# ZED-F9P_NEO-D9S_Combo.net
KiCad netlist of a schematic drawn in EAGLE
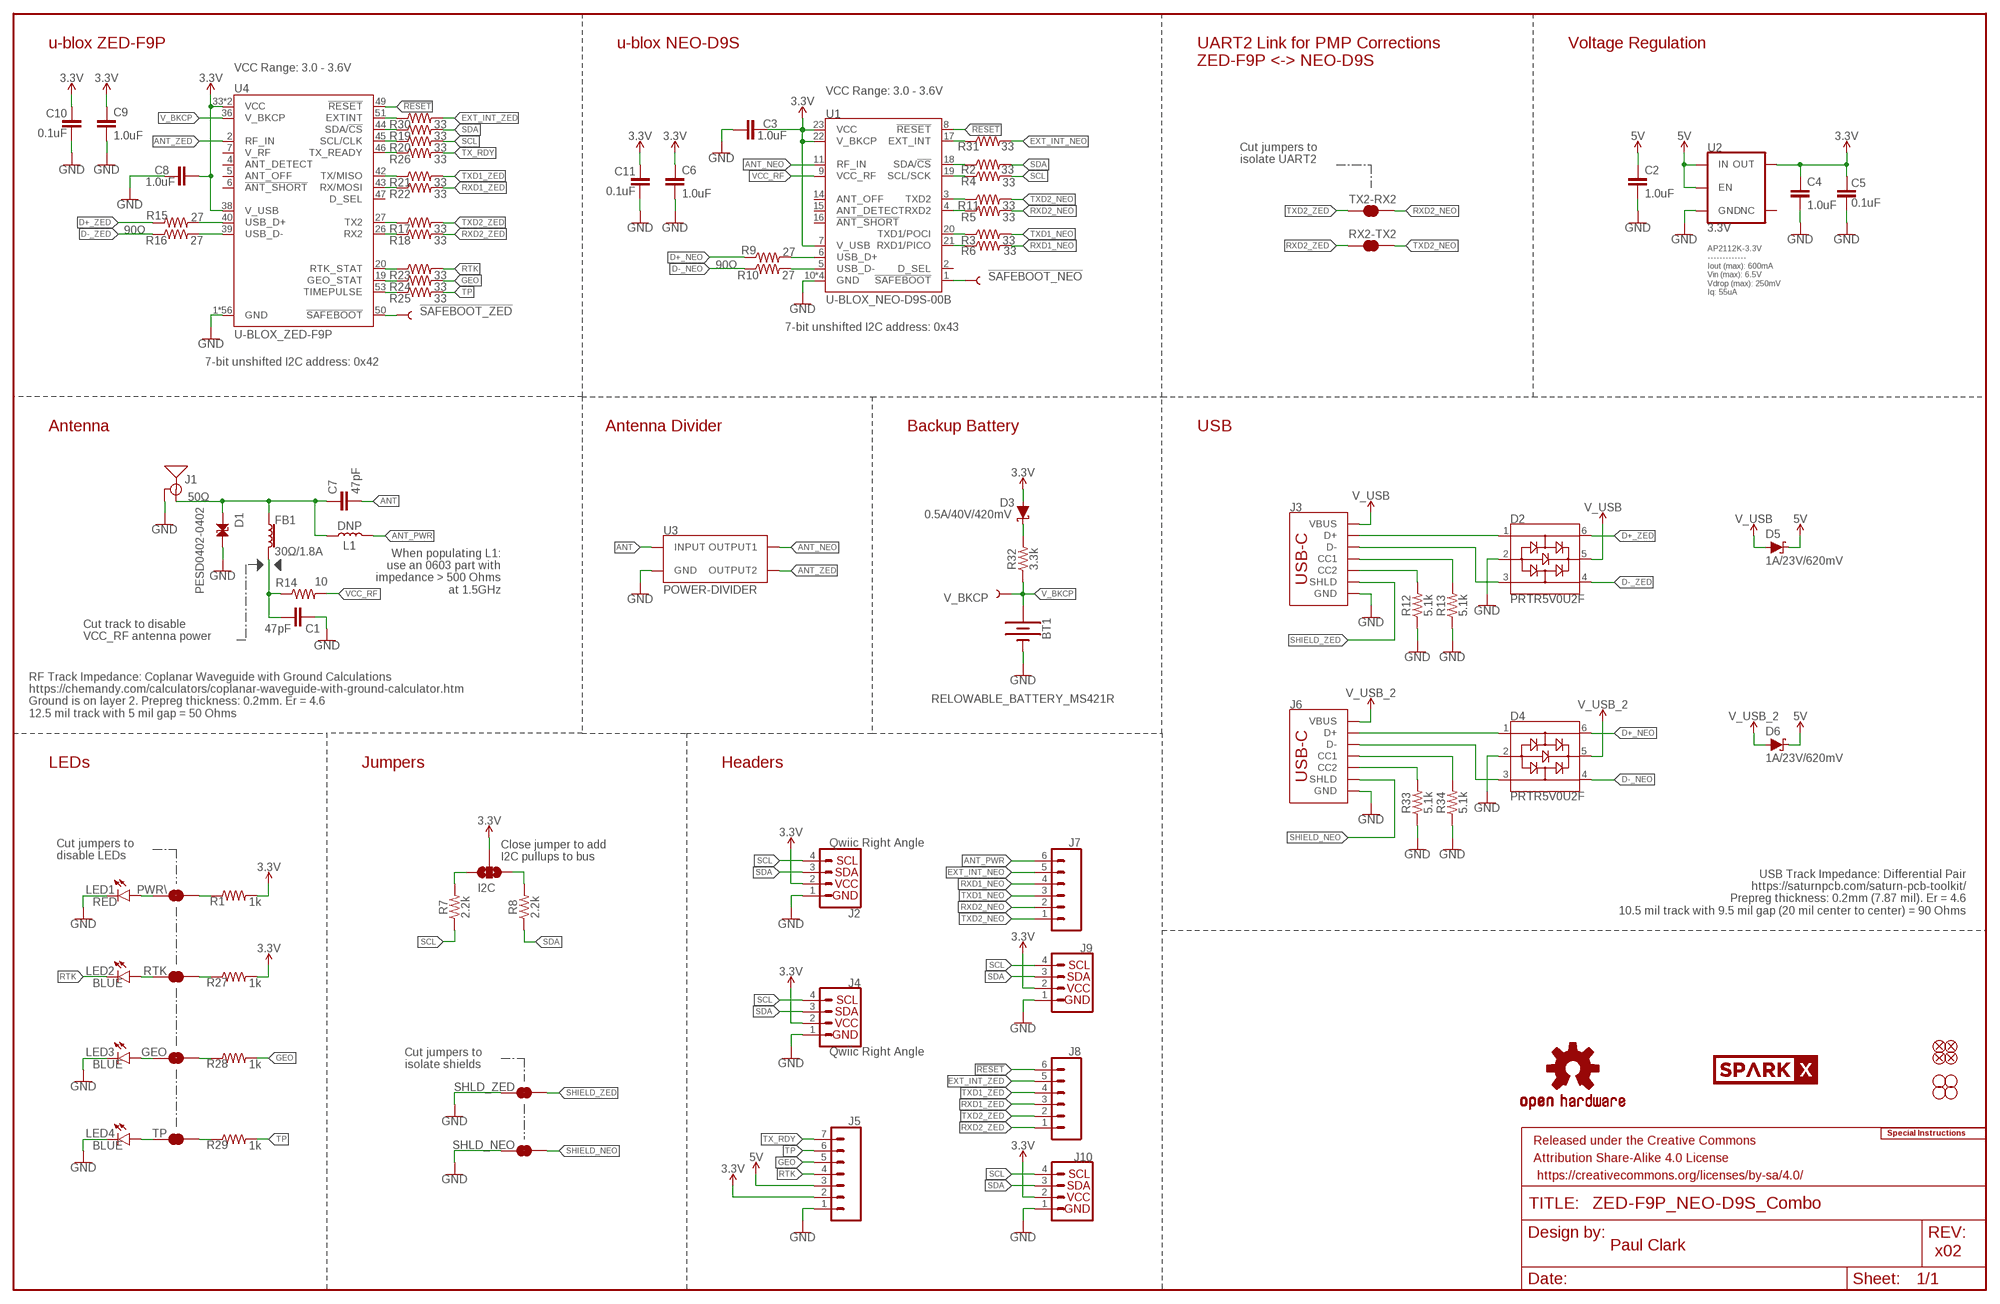
[diagram p0: schematic, sheet 1]

(export (version "E")
  (design (tool "Eeschema 10.0.6"))
  (components
    (comp (ref "!SAFEBOOT_NEO!")
      (value "TEST-POINTPOGO_PTH")
      (footprint "eagle-import:1X01_NO_SILK")
      (libsource (lib "eagle-import") (part "TEST-POINTPOGO_PTH"))
    )
    (comp (ref "!SAFEBOOT_ZED!")
      (value "TEST-POINTPOGO_PTH")
      (footprint "eagle-import:1X01_NO_SILK")
      (libsource (lib "eagle-import") (part "TEST-POINTPOGO_PTH"))
    )
    (comp (ref "BT1")
      (value "RELOWABLE_BATTERY_MS421R")
      (footprint "eagle-import:MS421R_IV03E")
      (libsource (lib "eagle-import") (part "RELOWABLE_BATTERY_MS421R"))
    )
    (comp (ref "C1")
      (value "47pF")
      (footprint "eagle-import:0603")
      (libsource (lib "eagle-import") (part "47PF-0603-50V-5%"))
    )
    (comp (ref "C2")
      (value "1.0uF")
      (footprint "eagle-import:0603")
      (libsource (lib "eagle-import") (part "1.0UF-0603-16V-10%"))
    )
    (comp (ref "C3")
      (value "1.0uF")
      (footprint "eagle-import:0603")
      (libsource (lib "eagle-import") (part "1.0UF-0603-16V-10%"))
    )
    (comp (ref "C4")
      (value "1.0uF")
      (footprint "eagle-import:0603")
      (libsource (lib "eagle-import") (part "1.0UF-0603-16V-10%"))
    )
    (comp (ref "C5")
      (value "0.1uF")
      (footprint "eagle-import:0603")
      (libsource (lib "eagle-import") (part "0.1UF-0603-25V-(+80/-20%)"))
    )
    (comp (ref "C6")
      (value "1.0uF")
      (footprint "eagle-import:0603")
      (libsource (lib "eagle-import") (part "1.0UF-0603-16V-10%"))
    )
    (comp (ref "C7")
      (value "47pF")
      (footprint "eagle-import:0603")
      (libsource (lib "eagle-import") (part "47PF-0603-50V-5%"))
    )
    (comp (ref "C8")
      (value "1.0uF")
      (footprint "eagle-import:0603")
      (libsource (lib "eagle-import") (part "1.0UF-0603-16V-10%"))
    )
    (comp (ref "C9")
      (value "1.0uF")
      (footprint "eagle-import:0603")
      (libsource (lib "eagle-import") (part "1.0UF-0603-16V-10%"))
    )
    (comp (ref "C10")
      (value "0.1uF")
      (footprint "eagle-import:0603")
      (libsource (lib "eagle-import") (part "0.1UF-0603-25V-(+80/-20%)"))
    )
    (comp (ref "C11")
      (value "0.1uF")
      (footprint "eagle-import:0603")
      (libsource (lib "eagle-import") (part "0.1UF-0603-25V-(+80/-20%)"))
    )
    (comp (ref "D1")
      (value "PESD0402-0402")
      (footprint "eagle-import:0402")
      (fields
        (field (name "DIGIKEY_PART") "PESD0402-140CT-ND")
        (field (name "MOUSE_PART") "650-PESD0402-140")
      )
      (libsource (lib "eagle-import") (part "PESD0402-0402"))
    )
    (comp (ref "D2")
      (value "PRTR5V0U2F")
      (footprint "eagle-import:SOT886")
      (libsource (lib "eagle-import") (part "PRTR5V0U2F"))
    )
    (comp (ref "D3")
      (value "0.5A/40V/420mV")
      (footprint "eagle-import:SOD-323")
      (libsource (lib "eagle-import") (part "DIODE-SCHOTTKY-PMEG4005EJ"))
    )
    (comp (ref "D4")
      (value "PRTR5V0U2F")
      (footprint "eagle-import:SOT886")
      (libsource (lib "eagle-import") (part "PRTR5V0U2F"))
    )
    (comp (ref "D5")
      (value "1A/23V/620mV")
      (footprint "eagle-import:SOD-323")
      (libsource (lib "eagle-import") (part "DIODE-SCHOTTKY-BAT20J"))
    )
    (comp (ref "D6")
      (value "1A/23V/620mV")
      (footprint "eagle-import:SOD-323")
      (libsource (lib "eagle-import") (part "DIODE-SCHOTTKY-BAT20J"))
    )
    (comp (ref "FB1")
      (value "30Ω/1.8A")
      (footprint "eagle-import:0603")
      (libsource (lib "eagle-import") (part "FERRITE_BEAD-0603"))
    )
    (comp (ref "FRAME2")
      (value "FRAME-LEDGER")
      (footprint "eagle-import:CREATIVE_COMMONS")
      (libsource (lib "eagle-import") (part "FRAME-LEDGER"))
    )
    (comp (ref "GEO")
      (value "JUMPER-SMT_2_NC_TRACE_SILK")
      (footprint "eagle-import:SMT-JUMPER_2_NC_TRACE_SILK")
      (libsource (lib "eagle-import") (part "JUMPER-SMT_2_NC_TRACE_SILK"))
    )
    (comp (ref "I2C")
      (value "JUMPER-SMT_3_NO_SILK")
      (footprint "eagle-import:SMT-JUMPER_3_NO_SILK")
      (libsource (lib "eagle-import") (part "JUMPER-SMT_3_NO_SILK"))
    )
    (comp (ref "J1")
      (value "ANTENNA-SMA-GROUNDEDEDGE_SMA")
      (footprint "eagle-import:SMA-EDGE")
      (libsource (lib "eagle-import") (part "ANTENNA-SMA-GROUNDEDEDGE_SMA"))
    )
    (comp (ref "J2")
      (value "Qwiic Right Angle")
      (footprint "eagle-import:JST04_1MM_RA")
      (libsource (lib "eagle-import") (part "I2C_STANDARDQWIIC"))
    )
    (comp (ref "J3")
      (value "USB Female Type C Connector")
      (footprint "eagle-import:USB-C-16P_4LAYER-PADS")
      (libsource (lib "eagle-import") (part "USB_C_4-LAYER_PADS"))
    )
    (comp (ref "J4")
      (value "Qwiic Right Angle")
      (footprint "eagle-import:JST04_1MM_RA")
      (libsource (lib "eagle-import") (part "I2C_STANDARDQWIIC"))
    )
    (comp (ref "J5")
      (value "CONN_07NO_SILK")
      (footprint "eagle-import:1X07_NO_SILK")
      (libsource (lib "eagle-import") (part "CONN_07NO_SILK"))
    )
    (comp (ref "J6")
      (value "USB Female Type C Connector")
      (footprint "eagle-import:USB-C-16P_4LAYER-PADS")
      (libsource (lib "eagle-import") (part "USB_C_4-LAYER_PADS"))
    )
    (comp (ref "J7")
      (value "CONN_06NO_SILK_FEMALE_PTH")
      (footprint "eagle-import:1X06_NO_SILK")
      (libsource (lib "eagle-import") (part "CONN_06NO_SILK_FEMALE_PTH"))
    )
    (comp (ref "J8")
      (value "CONN_06NO_SILK_FEMALE_PTH")
      (footprint "eagle-import:1X06_NO_SILK")
      (libsource (lib "eagle-import") (part "CONN_06NO_SILK_FEMALE_PTH"))
    )
    (comp (ref "J9")
      (value "I2C_STANDARD_NO_SILK")
      (footprint "eagle-import:1X04_NO_SILK")
      (libsource (lib "eagle-import") (part "I2C_STANDARD_NO_SILK"))
    )
    (comp (ref "J10")
      (value "I2C_STANDARD_NO_SILK")
      (footprint "eagle-import:1X04_NO_SILK")
      (libsource (lib "eagle-import") (part "I2C_STANDARD_NO_SILK"))
    )
    (comp (ref "JP21")
      (value "FIDUCIALUFIDUCIAL")
      (footprint "eagle-import:MICRO-FIDUCIAL")
      (libsource (lib "eagle-import") (part "FIDUCIALUFIDUCIAL"))
    )
    (comp (ref "JP31")
      (value "STAND-OFF")
      (footprint "eagle-import:STAND-OFF")
      (libsource (lib "eagle-import") (part "STAND-OFF"))
    )
    (comp (ref "JP41")
      (value "STAND-OFF")
      (footprint "eagle-import:STAND-OFF")
      (libsource (lib "eagle-import") (part "STAND-OFF"))
    )
    (comp (ref "JP61")
      (value "FIDUCIALUFIDUCIAL")
      (footprint "eagle-import:MICRO-FIDUCIAL")
      (libsource (lib "eagle-import") (part "FIDUCIALUFIDUCIAL"))
    )
    (comp (ref "JP71")
      (value "FIDUCIALUFIDUCIAL")
      (footprint "eagle-import:MICRO-FIDUCIAL")
      (libsource (lib "eagle-import") (part "FIDUCIALUFIDUCIAL"))
    )
    (comp (ref "JP81")
      (value "FIDUCIALUFIDUCIAL")
      (footprint "eagle-import:MICRO-FIDUCIAL")
      (libsource (lib "eagle-import") (part "FIDUCIALUFIDUCIAL"))
    )
    (comp (ref "JP91")
      (value "STAND-OFF")
      (footprint "eagle-import:STAND-OFF")
      (libsource (lib "eagle-import") (part "STAND-OFF"))
    )
    (comp (ref "JP101")
      (value "STAND-OFF")
      (footprint "eagle-import:STAND-OFF")
      (libsource (lib "eagle-import") (part "STAND-OFF"))
    )
    (comp (ref "L1")
      (value "DNP")
      (footprint "eagle-import:0603_NO-CREAM")
      (libsource (lib "eagle-import") (part "DNP-0603_NO-CREAM"))
    )
    (comp (ref "LED1")
      (value "RED")
      (footprint "eagle-import:LED-0603")
      (libsource (lib "eagle-import") (part "LED-RED0603"))
    )
    (comp (ref "LED2")
      (value "BLUE")
      (footprint "eagle-import:LED-0603")
      (libsource (lib "eagle-import") (part "LED-BLUE0603"))
    )
    (comp (ref "LED3")
      (value "BLUE")
      (footprint "eagle-import:LED-0603")
      (libsource (lib "eagle-import") (part "LED-BLUE0603"))
    )
    (comp (ref "LED4")
      (value "BLUE")
      (footprint "eagle-import:LED-0603")
      (libsource (lib "eagle-import") (part "LED-BLUE0603"))
    )
    (comp (ref "LOGO4")
      (value "OSHW-LOGOS")
      (footprint "eagle-import:OSHW-LOGO-S")
      (libsource (lib "eagle-import") (part "OSHW-LOGOS"))
    )
    (comp (ref "LOGO5")
      (value "SPECIAL_INSTRUCTIONS-ORDERING")
      (footprint "eagle-import:ORDERING_INSTRUCTIONS")
      (libsource (lib "eagle-import") (part "SPECIAL_INSTRUCTIONS-ORDERING"))
    )
    (comp (ref "PWR\\")
      (value "JUMPER-SMT_2_NC_TRACE_SILK")
      (footprint "eagle-import:SMT-JUMPER_2_NC_TRACE_SILK")
      (libsource (lib "eagle-import") (part "JUMPER-SMT_2_NC_TRACE_SILK"))
    )
    (comp (ref "R1")
      (value "1k")
      (footprint "eagle-import:0603")
      (libsource (lib "eagle-import") (part "1KOHM-0603-1/10W-1%"))
    )
    (comp (ref "R2")
      (value "33")
      (footprint "eagle-import:0603")
      (libsource (lib "eagle-import") (part "33OHM-0603-1/10W-1%"))
    )
    (comp (ref "R3")
      (value "33")
      (footprint "eagle-import:0603")
      (libsource (lib "eagle-import") (part "33OHM-0603-1/10W-1%"))
    )
    (comp (ref "R4")
      (value "33")
      (footprint "eagle-import:0603")
      (libsource (lib "eagle-import") (part "33OHM-0603-1/10W-1%"))
    )
    (comp (ref "R5")
      (value "33")
      (footprint "eagle-import:0603")
      (libsource (lib "eagle-import") (part "33OHM-0603-1/10W-1%"))
    )
    (comp (ref "R6")
      (value "33")
      (footprint "eagle-import:0603")
      (libsource (lib "eagle-import") (part "33OHM-0603-1/10W-1%"))
    )
    (comp (ref "R7")
      (value "2.2k")
      (footprint "eagle-import:0603")
      (libsource (lib "eagle-import") (part "2.2KOHM-0603-1/10W-1%"))
    )
    (comp (ref "R8")
      (value "2.2k")
      (footprint "eagle-import:0603")
      (libsource (lib "eagle-import") (part "2.2KOHM-0603-1/10W-1%"))
    )
    (comp (ref "R9")
      (value "27")
      (footprint "eagle-import:0603")
      (libsource (lib "eagle-import") (part "27OHM-0603-1/10W-1%"))
    )
    (comp (ref "R10")
      (value "27")
      (footprint "eagle-import:0603")
      (libsource (lib "eagle-import") (part "27OHM-0603-1/10W-1%"))
    )
    (comp (ref "R11")
      (value "33")
      (footprint "eagle-import:0603")
      (libsource (lib "eagle-import") (part "33OHM-0603-1/10W-1%"))
    )
    (comp (ref "R12")
      (value "5.1k")
      (footprint "eagle-import:0603")
      (libsource (lib "eagle-import") (part "5.1KOHM5.1KOHM-0603-1/10W-1%"))
    )
    (comp (ref "R13")
      (value "5.1k")
      (footprint "eagle-import:0603")
      (libsource (lib "eagle-import") (part "5.1KOHM5.1KOHM-0603-1/10W-1%"))
    )
    (comp (ref "R14")
      (value "10")
      (footprint "eagle-import:0603")
      (libsource (lib "eagle-import") (part "10OHM-0603-1/10W-1%"))
    )
    (comp (ref "R15")
      (value "27")
      (footprint "eagle-import:0603")
      (libsource (lib "eagle-import") (part "27OHM-0603-1/10W-1%"))
    )
    (comp (ref "R16")
      (value "27")
      (footprint "eagle-import:0603")
      (libsource (lib "eagle-import") (part "27OHM-0603-1/10W-1%"))
    )
    (comp (ref "R17")
      (value "33")
      (footprint "eagle-import:0603")
      (libsource (lib "eagle-import") (part "33OHM-0603-1/10W-1%"))
    )
    (comp (ref "R18")
      (value "33")
      (footprint "eagle-import:0603")
      (libsource (lib "eagle-import") (part "33OHM-0603-1/10W-1%"))
    )
    (comp (ref "R19")
      (value "33")
      (footprint "eagle-import:0603")
      (libsource (lib "eagle-import") (part "33OHM-0603-1/10W-1%"))
    )
    (comp (ref "R20")
      (value "33")
      (footprint "eagle-import:0603")
      (libsource (lib "eagle-import") (part "33OHM-0603-1/10W-1%"))
    )
    (comp (ref "R21")
      (value "33")
      (footprint "eagle-import:0603")
      (libsource (lib "eagle-import") (part "33OHM-0603-1/10W-1%"))
    )
    (comp (ref "R22")
      (value "33")
      (footprint "eagle-import:0603")
      (libsource (lib "eagle-import") (part "33OHM-0603-1/10W-1%"))
    )
    (comp (ref "R23")
      (value "33")
      (footprint "eagle-import:0603")
      (libsource (lib "eagle-import") (part "33OHM-0603-1/10W-1%"))
    )
    (comp (ref "R24")
      (value "33")
      (footprint "eagle-import:0603")
      (libsource (lib "eagle-import") (part "33OHM-0603-1/10W-1%"))
    )
    (comp (ref "R25")
      (value "33")
      (footprint "eagle-import:0603")
      (libsource (lib "eagle-import") (part "33OHM-0603-1/10W-1%"))
    )
    (comp (ref "R26")
      (value "33")
      (footprint "eagle-import:0603")
      (libsource (lib "eagle-import") (part "33OHM-0603-1/10W-1%"))
    )
    (comp (ref "R27")
      (value "1k")
      (footprint "eagle-import:0603")
      (libsource (lib "eagle-import") (part "1KOHM-0603-1/10W-1%"))
    )
    (comp (ref "R28")
      (value "1k")
      (footprint "eagle-import:0603")
      (libsource (lib "eagle-import") (part "1KOHM-0603-1/10W-1%"))
    )
    (comp (ref "R29")
      (value "1k")
      (footprint "eagle-import:0603")
      (libsource (lib "eagle-import") (part "1KOHM-0603-1/10W-1%"))
    )
    (comp (ref "R30")
      (value "33")
      (footprint "eagle-import:0603")
      (libsource (lib "eagle-import") (part "33OHM-0603-1/10W-1%"))
    )
    (comp (ref "R31")
      (value "33")
      (footprint "eagle-import:0603")
      (libsource (lib "eagle-import") (part "33OHM-0603-1/10W-1%"))
    )
    (comp (ref "R32")
      (value "3.3k")
      (footprint "eagle-import:0603")
      (libsource (lib "eagle-import") (part "3.3KOHM-0603-1/10W-1%"))
    )
    (comp (ref "R33")
      (value "5.1k")
      (footprint "eagle-import:0603")
      (libsource (lib "eagle-import") (part "5.1KOHM5.1KOHM-0603-1/10W-1%"))
    )
    (comp (ref "R34")
      (value "5.1k")
      (footprint "eagle-import:0603")
      (libsource (lib "eagle-import") (part "5.1KOHM5.1KOHM-0603-1/10W-1%"))
    )
    (comp (ref "RTK")
      (value "JUMPER-SMT_2_NC_TRACE_SILK")
      (footprint "eagle-import:SMT-JUMPER_2_NC_TRACE_SILK")
      (libsource (lib "eagle-import") (part "JUMPER-SMT_2_NC_TRACE_SILK"))
    )
    (comp (ref "RX2-TX2")
      (value "JUMPER-SMT_2_NC_TRACE_SILK")
      (footprint "eagle-import:SMT-JUMPER_2_NC_TRACE_SILK")
      (libsource (lib "eagle-import") (part "JUMPER-SMT_2_NC_TRACE_SILK"))
    )
    (comp (ref "SHLD_NEO")
      (value "JUMPER-SMT_2_NC_TRACE_SILK")
      (footprint "eagle-import:SMT-JUMPER_2_NC_TRACE_SILK")
      (libsource (lib "eagle-import") (part "JUMPER-SMT_2_NC_TRACE_SILK"))
    )
    (comp (ref "SHLD_ZED")
      (value "JUMPER-SMT_2_NC_TRACE_SILK")
      (footprint "eagle-import:SMT-JUMPER_2_NC_TRACE_SILK")
      (libsource (lib "eagle-import") (part "JUMPER-SMT_2_NC_TRACE_SILK"))
    )
    (comp (ref "TP")
      (value "JUMPER-SMT_2_NC_TRACE_SILK")
      (footprint "eagle-import:SMT-JUMPER_2_NC_TRACE_SILK")
      (libsource (lib "eagle-import") (part "JUMPER-SMT_2_NC_TRACE_SILK"))
    )
    (comp (ref "TX2-RX2")
      (value "JUMPER-SMT_2_NC_TRACE_SILK")
      (footprint "eagle-import:SMT-JUMPER_2_NC_TRACE_SILK")
      (libsource (lib "eagle-import") (part "JUMPER-SMT_2_NC_TRACE_SILK"))
    )
    (comp (ref "U$77")
      (value "SPARKX-LOGO4")
      (footprint "eagle-import:SPARKX-MEDIUM")
      (libsource (lib "eagle-import") (part "SPARKX-LOGO4"))
    )
    (comp (ref "U$78")
      (value "SPARKX-LOGO4")
      (footprint "eagle-import:SPARKX-MEDIUM")
      (libsource (lib "eagle-import") (part "SPARKX-LOGO4"))
    )
    (comp (ref "U1")
      (value "U-BLOX_NEO-D9S-00B")
      (footprint "eagle-import:NEO-M9N_M8T_M8U_D9S")
      (libsource (lib "eagle-import") (part "U-BLOX_NEO-D9S-00B"))
    )
    (comp (ref "U2")
      (value "3.3V")
      (footprint "eagle-import:SOT23-5")
      (libsource (lib "eagle-import") (part "V_REG_AP2112K-3.3V"))
    )
    (comp (ref "U3")
      (value "POWER-DIVIDER")
      (footprint "eagle-import:PD0922J5050S2HF_ANA")
      (fields (field (name "MANUFACTURER_PART_NUMBER") "PD0922J5050S2HF"))
      (libsource (lib "eagle-import") (part "POWER-DIVIDER"))
    )
    (comp (ref "U4")
      (value "U-BLOX_ZED-F9P")
      (footprint "eagle-import:ZED-F9P")
      (libsource (lib "eagle-import") (part "U-BLOX_ZED-F9P"))
    )
    (comp (ref "V_BKCP")
      (value "TEST-POINT3X5")
      (footprint "eagle-import:PAD.03X.05")
      (libsource (lib "eagle-import") (part "TEST-POINT3X5"))
    )
  )
  (nets
    (net (code "1") (name "/~{RESET}") (class "Default")
      (node (ref "J8") (pin "6") (pinfunction "6_6") (pintype "passive"))
      (node (ref "U1") (pin "8") (pinfunction "~{RESET}_8") (pintype "input"))
      (node (ref "U4") (pin "49") (pinfunction "~{RESET}_49") (pintype "bidirectional"))
    )
    (net (code "2") (name "3.3V") (class "Default")
      (node (ref "C10") (pin "2") (pinfunction "2_2") (pintype "passive"))
      (node (ref "C11") (pin "2") (pinfunction "2_2") (pintype "passive"))
      (node (ref "C3") (pin "1") (pinfunction "1_1") (pintype "passive"))
      (node (ref "C4") (pin "1") (pinfunction "1_1") (pintype "passive"))
      (node (ref "C5") (pin "2") (pinfunction "2_2") (pintype "passive"))
      (node (ref "C6") (pin "1") (pinfunction "1_1") (pintype "passive"))
      (node (ref "C8") (pin "2") (pinfunction "2_2") (pintype "passive"))
      (node (ref "C9") (pin "1") (pinfunction "1_1") (pintype "passive"))
      (node (ref "D3") (pin "A") (pinfunction "A_A") (pintype "passive"))
      (node (ref "I2C") (pin "2") (pinfunction "2_2") (pintype "passive"))
      (node (ref "J10") (pin "2") (pinfunction "2_2") (pintype "power_in"))
      (node (ref "J2") (pin "2") (pinfunction "2_2") (pintype "power_in"))
      (node (ref "J4") (pin "2") (pinfunction "2_2") (pintype "power_in"))
      (node (ref "J5") (pin "2") (pinfunction "2_2") (pintype "passive"))
      (node (ref "J9") (pin "2") (pinfunction "2_2") (pintype "power_in"))
      (node (ref "R1") (pin "2") (pinfunction "2_2") (pintype "passive"))
      (node (ref "R27") (pin "2") (pinfunction "2_2") (pintype "passive"))
      (node (ref "U1") (pin "22") (pinfunction "V_BKCP_22") (pintype "power_in"))
      (node (ref "U1") (pin "23") (pinfunction "VCC_23") (pintype "power_in"))
      (node (ref "U1") (pin "7") (pinfunction "V_USB_7") (pintype "power_in"))
      (node (ref "U2") (pin "5") (pinfunction "OUT_5") (pintype "passive"))
      (node (ref "U4") (pin "33") (pinfunction "VCC_33") (pintype "bidirectional"))
      (node (ref "U4") (pin "34") (pinfunction "VCC_34") (pintype "bidirectional"))
      (node (ref "U4") (pin "38") (pinfunction "V_USB_38") (pintype "bidirectional"))
    )
    (net (code "3") (name "5V") (class "Default")
      (node (ref "C2") (pin "1") (pinfunction "1_1") (pintype "passive"))
      (node (ref "D5") (pin "C") (pinfunction "C_C") (pintype "passive"))
      (node (ref "D6") (pin "C") (pinfunction "C_C") (pintype "passive"))
      (node (ref "J5") (pin "3") (pinfunction "3_3") (pintype "passive"))
      (node (ref "U2") (pin "1") (pinfunction "IN_1") (pintype "input"))
      (node (ref "U2") (pin "3") (pinfunction "EN_3") (pintype "input"))
    )
    (net (code "4") (name "ANT") (class "Default")
      (node (ref "C7") (pin "2") (pinfunction "2_2") (pintype "passive"))
      (node (ref "U3") (pin "2") (pinfunction "INPUT_2") (pintype "input"))
    )
    (net (code "5") (name "ANT_NEO") (class "Default")
      (node (ref "U1") (pin "11") (pinfunction "RF_IN_11") (pintype "input"))
      (node (ref "U3") (pin "4") (pinfunction "OUTPUT1_4") (pintype "output"))
    )
    (net (code "6") (name "ANT_PWR") (class "Default")
      (node (ref "J7") (pin "6") (pinfunction "6_6") (pintype "passive"))
      (node (ref "L1") (pin "2") (pinfunction "2_2") (pintype "passive"))
    )
    (net (code "7") (name "ANT_ZED") (class "Default")
      (node (ref "U3") (pin "6") (pinfunction "OUTPUT2_6") (pintype "output"))
      (node (ref "U4") (pin "2") (pinfunction "RF_IN_2") (pintype "bidirectional"))
    )
    (net (code "8") (name "D+_NEO") (class "Default")
      (node (ref "D4") (pin "6") (pinfunction "6_6") (pintype "bidirectional"))
      (node (ref "R9") (pin "1") (pinfunction "1_1") (pintype "passive"))
    )
    (net (code "9") (name "D+_ZED") (class "Default")
      (node (ref "D2") (pin "6") (pinfunction "6_6") (pintype "bidirectional"))
      (node (ref "R15") (pin "1") (pinfunction "1_1") (pintype "passive"))
    )
    (net (code "10") (name "D-_NEO") (class "Default")
      (node (ref "D4") (pin "4") (pinfunction "4_4") (pintype "bidirectional"))
      (node (ref "R10") (pin "1") (pinfunction "1_1") (pintype "passive"))
    )
    (net (code "11") (name "D-_ZED") (class "Default")
      (node (ref "D2") (pin "4") (pinfunction "4_4") (pintype "bidirectional"))
      (node (ref "R16") (pin "1") (pinfunction "1_1") (pintype "passive"))
    )
    (net (code "12") (name "EXT_INT_NEO") (class "Default")
      (node (ref "J7") (pin "5") (pinfunction "5_5") (pintype "passive"))
      (node (ref "R31") (pin "2") (pinfunction "2_2") (pintype "passive"))
    )
    (net (code "13") (name "EXT_INT_ZED") (class "Default")
      (node (ref "J8") (pin "5") (pinfunction "5_5") (pintype "passive"))
      (node (ref "R30") (pin "2") (pinfunction "2_2") (pintype "passive"))
    )
    (net (code "14") (name "GEO") (class "Default")
      (node (ref "J5") (pin "5") (pinfunction "5_5") (pintype "passive"))
      (node (ref "R24") (pin "2") (pinfunction "2_2") (pintype "passive"))
      (node (ref "R28") (pin "2") (pinfunction "2_2") (pintype "passive"))
    )
    (net (code "15") (name "GND") (class "Default")
      (node (ref "BT1") (pin "-") (pinfunction "-_-") (pintype "power_in"))
      (node (ref "C1") (pin "2") (pinfunction "2_2") (pintype "passive"))
      (node (ref "C10") (pin "1") (pinfunction "1_1") (pintype "passive"))
      (node (ref "C11") (pin "1") (pinfunction "1_1") (pintype "passive"))
      (node (ref "C2") (pin "2") (pinfunction "2_2") (pintype "passive"))
      (node (ref "C3") (pin "2") (pinfunction "2_2") (pintype "passive"))
      (node (ref "C4") (pin "2") (pinfunction "2_2") (pintype "passive"))
      (node (ref "C5") (pin "1") (pinfunction "1_1") (pintype "passive"))
      (node (ref "C6") (pin "2") (pinfunction "2_2") (pintype "passive"))
      (node (ref "C8") (pin "1") (pinfunction "1_1") (pintype "passive"))
      (node (ref "C9") (pin "2") (pinfunction "2_2") (pintype "passive"))
      (node (ref "D1") (pin "2") (pinfunction "2_2") (pintype "bidirectional"))
      (node (ref "D2") (pin "2") (pinfunction "2_2") (pintype "power_in"))
      (node (ref "D4") (pin "2") (pinfunction "2_2") (pintype "power_in"))
      (node (ref "J1") (pin "GND@0") (pinfunction "GND_GND@0") (pintype "bidirectional"))
      (node (ref "J1") (pin "GND@1") (pinfunction "GND_GND@1") (pintype "bidirectional"))
      (node (ref "J1") (pin "GND@2") (pinfunction "GND_GND@2") (pintype "bidirectional"))
      (node (ref "J1") (pin "GND@3") (pinfunction "GND_GND@3") (pintype "bidirectional"))
      (node (ref "J10") (pin "1") (pinfunction "1_1") (pintype "power_in"))
      (node (ref "J2") (pin "1") (pinfunction "1_1") (pintype "power_in"))
      (node (ref "J3") (pin "GND") (pinfunction "GND_GND") (pintype "bidirectional"))
      (node (ref "J3") (pin "GND2") (pinfunction "GND_GND2") (pintype "bidirectional"))
      (node (ref "J4") (pin "1") (pinfunction "1_1") (pintype "power_in"))
      (node (ref "J5") (pin "1") (pinfunction "1_1") (pintype "passive"))
      (node (ref "J6") (pin "GND") (pinfunction "GND_GND") (pintype "bidirectional"))
      (node (ref "J6") (pin "GND2") (pinfunction "GND_GND2") (pintype "bidirectional"))
      (node (ref "J9") (pin "1") (pinfunction "1_1") (pintype "power_in"))
      (node (ref "LED1") (pin "C") (pinfunction "C_C") (pintype "passive"))
      (node (ref "LED3") (pin "C") (pinfunction "C_C") (pintype "passive"))
      (node (ref "LED4") (pin "C") (pinfunction "C_C") (pintype "passive"))
      (node (ref "R12") (pin "1") (pinfunction "1_1") (pintype "passive"))
      (node (ref "R13") (pin "1") (pinfunction "1_1") (pintype "passive"))
      (node (ref "R33") (pin "1") (pinfunction "1_1") (pintype "passive"))
      (node (ref "R34") (pin "1") (pinfunction "1_1") (pintype "passive"))
      (node (ref "SHLD_NEO") (pin "1") (pinfunction "1_1") (pintype "passive"))
      (node (ref "SHLD_ZED") (pin "1") (pinfunction "1_1") (pintype "passive"))
      (node (ref "U1") (pin "10") (pinfunction "GND_10") (pintype "power_in"))
      (node (ref "U1") (pin "12") (pinfunction "GND_12") (pintype "power_in"))
      (node (ref "U1") (pin "13") (pinfunction "GND_13") (pintype "power_in"))
      (node (ref "U1") (pin "24") (pinfunction "GND_24") (pintype "power_in"))
      (node (ref "U2") (pin "2") (pinfunction "GND_2") (pintype "input"))
      (node (ref "U3") (pin "1") (pinfunction "GND_1") (pintype "passive"))
      (node (ref "U3") (pin "3") (pinfunction "GND_3") (pintype "passive"))
      (node (ref "U3") (pin "5") (pinfunction "GND_5") (pintype "passive"))
      (node (ref "U4") (pin "1") (pinfunction "GND_1") (pintype "bidirectional"))
      (node (ref "U4") (pin "100") (pinfunction "GND_100") (pintype "bidirectional"))
      (node (ref "U4") (pin "101") (pinfunction "GND_101") (pintype "bidirectional"))
      (node (ref "U4") (pin "102") (pinfunction "GND_102") (pintype "bidirectional"))
      (node (ref "U4") (pin "12") (pinfunction "GND_12") (pintype "bidirectional"))
      (node (ref "U4") (pin "14") (pinfunction "GND_14") (pintype "bidirectional"))
      (node (ref "U4") (pin "3") (pinfunction "GND_3") (pintype "bidirectional"))
      (node (ref "U4") (pin "32") (pinfunction "GND_32") (pintype "bidirectional"))
      (node (ref "U4") (pin "37") (pinfunction "GND_37") (pintype "bidirectional"))
      (node (ref "U4") (pin "41") (pinfunction "GND_41") (pintype "bidirectional"))
      (node (ref "U4") (pin "48") (pinfunction "GND_48") (pintype "bidirectional"))
      (node (ref "U4") (pin "55") (pinfunction "GND_55") (pintype "bidirectional"))
      (node (ref "U4") (pin "56") (pinfunction "GND_56") (pintype "bidirectional"))
      (node (ref "U4") (pin "57") (pinfunction "GND_57") (pintype "bidirectional"))
      (node (ref "U4") (pin "58") (pinfunction "GND_58") (pintype "bidirectional"))
      (node (ref "U4") (pin "59") (pinfunction "GND_59") (pintype "bidirectional"))
      (node (ref "U4") (pin "60") (pinfunction "GND_60") (pintype "bidirectional"))
      (node (ref "U4") (pin "61") (pinfunction "GND_61") (pintype "bidirectional"))
      (node (ref "U4") (pin "62") (pinfunction "GND_62") (pintype "bidirectional"))
      (node (ref "U4") (pin "63") (pinfunction "GND_63") (pintype "bidirectional"))
      (node (ref "U4") (pin "64") (pinfunction "GND_64") (pintype "bidirectional"))
      (node (ref "U4") (pin "65") (pinfunction "GND_65") (pintype "bidirectional"))
      (node (ref "U4") (pin "66") (pinfunction "GND_66") (pintype "bidirectional"))
      (node (ref "U4") (pin "67") (pinfunction "GND_67") (pintype "bidirectional"))
      (node (ref "U4") (pin "68") (pinfunction "GND_68") (pintype "bidirectional"))
      (node (ref "U4") (pin "69") (pinfunction "GND_69") (pintype "bidirectional"))
      (node (ref "U4") (pin "70") (pinfunction "GND_70") (pintype "bidirectional"))
      (node (ref "U4") (pin "71") (pinfunction "GND_71") (pintype "bidirectional"))
      (node (ref "U4") (pin "72") (pinfunction "GND_72") (pintype "bidirectional"))
      (node (ref "U4") (pin "73") (pinfunction "GND_73") (pintype "bidirectional"))
      (node (ref "U4") (pin "74") (pinfunction "GND_74") (pintype "bidirectional"))
      (node (ref "U4") (pin "75") (pinfunction "GND_75") (pintype "bidirectional"))
      (node (ref "U4") (pin "76") (pinfunction "GND_76") (pintype "bidirectional"))
      (node (ref "U4") (pin "77") (pinfunction "GND_77") (pintype "bidirectional"))
      (node (ref "U4") (pin "78") (pinfunction "GND_78") (pintype "bidirectional"))
      (node (ref "U4") (pin "79") (pinfunction "GND_79") (pintype "bidirectional"))
      (node (ref "U4") (pin "80") (pinfunction "GND_80") (pintype "bidirectional"))
      (node (ref "U4") (pin "81") (pinfunction "GND_81") (pintype "bidirectional"))
      (node (ref "U4") (pin "82") (pinfunction "GND_82") (pintype "bidirectional"))
      (node (ref "U4") (pin "83") (pinfunction "GND_83") (pintype "bidirectional"))
      (node (ref "U4") (pin "84") (pinfunction "GND_84") (pintype "bidirectional"))
      (node (ref "U4") (pin "85") (pinfunction "GND_85") (pintype "bidirectional"))
      (node (ref "U4") (pin "86") (pinfunction "GND_86") (pintype "bidirectional"))
      (node (ref "U4") (pin "87") (pinfunction "GND_87") (pintype "bidirectional"))
      (node (ref "U4") (pin "88") (pinfunction "GND_88") (pintype "bidirectional"))
      (node (ref "U4") (pin "89") (pinfunction "GND_89") (pintype "bidirectional"))
      (node (ref "U4") (pin "90") (pinfunction "GND_90") (pintype "bidirectional"))
      (node (ref "U4") (pin "91") (pinfunction "GND_91") (pintype "bidirectional"))
      (node (ref "U4") (pin "92") (pinfunction "GND_92") (pintype "bidirectional"))
      (node (ref "U4") (pin "93") (pinfunction "GND_93") (pintype "bidirectional"))
      (node (ref "U4") (pin "94") (pinfunction "GND_94") (pintype "bidirectional"))
      (node (ref "U4") (pin "95") (pinfunction "GND_95") (pintype "bidirectional"))
      (node (ref "U4") (pin "96") (pinfunction "GND_96") (pintype "bidirectional"))
      (node (ref "U4") (pin "97") (pinfunction "GND_97") (pintype "bidirectional"))
      (node (ref "U4") (pin "98") (pinfunction "GND_98") (pintype "bidirectional"))
      (node (ref "U4") (pin "99") (pinfunction "GND_99") (pintype "bidirectional"))
    )
    (net (code "16") (name "Net-(C1-Pad1)") (class "Default")
      (node (ref "C1") (pin "1") (pinfunction "1_1") (pintype "passive"))
      (node (ref "FB1") (pin "2") (pinfunction "2_2") (pintype "passive"))
      (node (ref "R14") (pin "1") (pinfunction "1_1") (pintype "passive"))
    )
    (net (code "17") (name "Net-(D2-Pad1)") (class "Default")
      (node (ref "D2") (pin "1") (pinfunction "1_1") (pintype "bidirectional"))
      (node (ref "J3") (pin "A6") (pinfunction "D+_A6") (pintype "bidirectional"))
      (node (ref "J3") (pin "B6") (pinfunction "D+_B6") (pintype "bidirectional"))
    )
    (net (code "18") (name "Net-(D2-Pad3)") (class "Default")
      (node (ref "D2") (pin "3") (pinfunction "3_3") (pintype "bidirectional"))
      (node (ref "J3") (pin "A7") (pinfunction "D-_A7") (pintype "bidirectional"))
      (node (ref "J3") (pin "B7") (pinfunction "D-_B7") (pintype "bidirectional"))
    )
    (net (code "19") (name "Net-(D3-PadC)") (class "Default")
      (node (ref "D3") (pin "C") (pinfunction "C_C") (pintype "passive"))
      (node (ref "R32") (pin "2") (pinfunction "2_2") (pintype "passive"))
    )
    (net (code "20") (name "Net-(D4-Pad1)") (class "Default")
      (node (ref "D4") (pin "1") (pinfunction "1_1") (pintype "bidirectional"))
      (node (ref "J6") (pin "A6") (pinfunction "D+_A6") (pintype "bidirectional"))
      (node (ref "J6") (pin "B6") (pinfunction "D+_B6") (pintype "bidirectional"))
    )
    (net (code "21") (name "Net-(D4-Pad3)") (class "Default")
      (node (ref "D4") (pin "3") (pinfunction "3_3") (pintype "bidirectional"))
      (node (ref "J6") (pin "A7") (pinfunction "D-_A7") (pintype "bidirectional"))
      (node (ref "J6") (pin "B7") (pinfunction "D-_B7") (pintype "bidirectional"))
    )
    (net (code "22") (name "Net-(GEO-Pad1)") (class "Default")
      (node (ref "GEO") (pin "1") (pinfunction "1_1") (pintype "passive"))
      (node (ref "LED3") (pin "A") (pinfunction "A_A") (pintype "passive"))
    )
    (net (code "23") (name "Net-(GEO-Pad2)") (class "Default")
      (node (ref "GEO") (pin "2") (pinfunction "2_2") (pintype "passive"))
      (node (ref "R28") (pin "1") (pinfunction "1_1") (pintype "passive"))
    )
    (net (code "24") (name "Net-(I2C-Pad1)") (class "Default")
      (node (ref "I2C") (pin "1") (pinfunction "1_1") (pintype "passive"))
      (node (ref "R8") (pin "2") (pinfunction "2_2") (pintype "passive"))
    )
    (net (code "25") (name "Net-(I2C-Pad3)") (class "Default")
      (node (ref "I2C") (pin "3") (pinfunction "3_3") (pintype "passive"))
      (node (ref "R7") (pin "2") (pinfunction "2_2") (pintype "passive"))
    )
    (net (code "26") (name "Net-(J1-SIGNAL)") (class "Default")
      (node (ref "C7") (pin "1") (pinfunction "1_1") (pintype "passive"))
      (node (ref "D1") (pin "1") (pinfunction "1_1") (pintype "bidirectional"))
      (node (ref "FB1") (pin "1") (pinfunction "1_1") (pintype "passive"))
      (node (ref "J1") (pin "SIG") (pinfunction "SIGNAL_SIG") (pintype "bidirectional"))
      (node (ref "L1") (pin "1") (pinfunction "1_1") (pintype "passive"))
    )
    (net (code "27") (name "Net-(J3-CC1)") (class "Default")
      (node (ref "J3") (pin "A5") (pinfunction "CC1_A5") (pintype "bidirectional"))
      (node (ref "R13") (pin "2") (pinfunction "2_2") (pintype "passive"))
    )
    (net (code "28") (name "Net-(J3-CC2)") (class "Default")
      (node (ref "J3") (pin "B5") (pinfunction "CC2_B5") (pintype "bidirectional"))
      (node (ref "R12") (pin "2") (pinfunction "2_2") (pintype "passive"))
    )
    (net (code "29") (name "Net-(J6-CC1)") (class "Default")
      (node (ref "J6") (pin "A5") (pinfunction "CC1_A5") (pintype "bidirectional"))
      (node (ref "R34") (pin "2") (pinfunction "2_2") (pintype "passive"))
    )
    (net (code "30") (name "Net-(J6-CC2)") (class "Default")
      (node (ref "J6") (pin "B5") (pinfunction "CC2_B5") (pintype "bidirectional"))
      (node (ref "R33") (pin "2") (pinfunction "2_2") (pintype "passive"))
    )
    (net (code "31") (name "Net-(LED1-PadA)") (class "Default")
      (node (ref "LED1") (pin "A") (pinfunction "A_A") (pintype "passive"))
      (node (ref "PWR\\") (pin "1") (pinfunction "1_1") (pintype "passive"))
    )
    (net (code "32") (name "Net-(LED2-PadA)") (class "Default")
      (node (ref "LED2") (pin "A") (pinfunction "A_A") (pintype "passive"))
      (node (ref "RTK") (pin "1") (pinfunction "1_1") (pintype "passive"))
    )
    (net (code "33") (name "Net-(LED4-PadA)") (class "Default")
      (node (ref "LED4") (pin "A") (pinfunction "A_A") (pintype "passive"))
      (node (ref "TP") (pin "1") (pinfunction "1_1") (pintype "passive"))
    )
    (net (code "34") (name "Net-(PWR\\-Pad2)") (class "Default")
      (node (ref "PWR\\") (pin "2") (pinfunction "2_2") (pintype "passive"))
      (node (ref "R1") (pin "1") (pinfunction "1_1") (pintype "passive"))
    )
    (net (code "35") (name "Net-(R27-Pad1)") (class "Default")
      (node (ref "R27") (pin "1") (pinfunction "1_1") (pintype "passive"))
      (node (ref "RTK") (pin "2") (pinfunction "2_2") (pintype "passive"))
    )
    (net (code "36") (name "Net-(R29-Pad1)") (class "Default")
      (node (ref "R29") (pin "1") (pinfunction "1_1") (pintype "passive"))
      (node (ref "TP") (pin "2") (pinfunction "2_2") (pintype "passive"))
    )
    (net (code "37") (name "Net-(U1-EXT_INT)") (class "Default")
      (node (ref "R31") (pin "1") (pinfunction "1_1") (pintype "passive"))
      (node (ref "U1") (pin "17") (pinfunction "EXT_INT_17") (pintype "input"))
    )
    (net (code "38") (name "Net-(U1-RXD1{slash}PICO)") (class "Default")
      (node (ref "R6") (pin "1") (pinfunction "1_1") (pintype "passive"))
      (node (ref "U1") (pin "21") (pinfunction "RXD1/PICO_21") (pintype "input"))
    )
    (net (code "39") (name "Net-(U1-RXD2)") (class "Default")
      (node (ref "R5") (pin "1") (pinfunction "1_1") (pintype "passive"))
      (node (ref "U1") (pin "4") (pinfunction "RXD2_4") (pintype "input"))
    )
    (net (code "40") (name "Net-(U1-SCL{slash}SCK)") (class "Default")
      (node (ref "R4") (pin "1") (pinfunction "1_1") (pintype "passive"))
      (node (ref "U1") (pin "19") (pinfunction "SCL/SCK_19") (pintype "bidirectional"))
    )
    (net (code "41") (name "Net-(U1-SDA{slash}~{CS})") (class "Default")
      (node (ref "R2") (pin "1") (pinfunction "1_1") (pintype "passive"))
      (node (ref "U1") (pin "18") (pinfunction "SDA/~{CS}_18") (pintype "bidirectional"))
    )
    (net (code "42") (name "Net-(U1-TXD1{slash}POCI)") (class "Default")
      (node (ref "R3") (pin "1") (pinfunction "1_1") (pintype "passive"))
      (node (ref "U1") (pin "20") (pinfunction "TXD1/POCI_20") (pintype "output"))
    )
    (net (code "43") (name "Net-(U1-TXD2)") (class "Default")
      (node (ref "R11") (pin "1") (pinfunction "1_1") (pintype "passive"))
      (node (ref "U1") (pin "3") (pinfunction "TXD2_3") (pintype "output"))
    )
    (net (code "44") (name "Net-(U1-USB_D+)") (class "Default")
      (node (ref "R9") (pin "2") (pinfunction "2_2") (pintype "passive"))
      (node (ref "U1") (pin "6") (pinfunction "USB_D+_6") (pintype "bidirectional"))
    )
    (net (code "45") (name "Net-(U1-USB_D-)") (class "Default")
      (node (ref "R10") (pin "2") (pinfunction "2_2") (pintype "passive"))
      (node (ref "U1") (pin "5") (pinfunction "USB_D-_5") (pintype "bidirectional"))
    )
    (net (code "46") (name "Net-(U1-~{SAFEBOOT})") (class "Default")
      (node (ref "!SAFEBOOT_NEO!") (pin "1") (pinfunction "1_1") (pintype "bidirectional"))
      (node (ref "U1") (pin "1") (pinfunction "~{SAFEBOOT}_1") (pintype "input"))
    )
    (net (code "47") (name "Net-(U4-EXTINT)") (class "Default")
      (node (ref "R30") (pin "1") (pinfunction "1_1") (pintype "passive"))
      (node (ref "U4") (pin "51") (pinfunction "EXTINT_51") (pintype "bidirectional"))
    )
    (net (code "48") (name "Net-(U4-GEO_STAT)") (class "Default")
      (node (ref "R24") (pin "1") (pinfunction "1_1") (pintype "passive"))
      (node (ref "U4") (pin "19") (pinfunction "GEO_STAT_19") (pintype "bidirectional"))
    )
    (net (code "49") (name "Net-(U4-RTK_STAT)") (class "Default")
      (node (ref "R23") (pin "1") (pinfunction "1_1") (pintype "passive"))
      (node (ref "U4") (pin "20") (pinfunction "RTK_STAT_20") (pintype "bidirectional"))
    )
    (net (code "50") (name "Net-(U4-RX2)") (class "Default")
      (node (ref "R18") (pin "1") (pinfunction "1_1") (pintype "passive"))
      (node (ref "U4") (pin "26") (pinfunction "RX2_26") (pintype "bidirectional"))
    )
    (net (code "51") (name "Net-(U4-RX{slash}MOSI)") (class "Default")
      (node (ref "R22") (pin "1") (pinfunction "1_1") (pintype "passive"))
      (node (ref "U4") (pin "43") (pinfunction "RX/MOSI_43") (pintype "bidirectional"))
    )
    (net (code "52") (name "Net-(U4-SCL{slash}CLK)") (class "Default")
      (node (ref "R20") (pin "1") (pinfunction "1_1") (pintype "passive"))
      (node (ref "U4") (pin "45") (pinfunction "SCL/CLK_45") (pintype "bidirectional"))
    )
    (net (code "53") (name "Net-(U4-SDA{slash}~{CS})") (class "Default")
      (node (ref "R19") (pin "1") (pinfunction "1_1") (pintype "passive"))
      (node (ref "U4") (pin "44") (pinfunction "SDA/~{CS}_44") (pintype "bidirectional"))
    )
    (net (code "54") (name "Net-(U4-TIMEPULSE)") (class "Default")
      (node (ref "R25") (pin "1") (pinfunction "1_1") (pintype "passive"))
      (node (ref "U4") (pin "53") (pinfunction "TIMEPULSE_53") (pintype "bidirectional"))
    )
    (net (code "55") (name "Net-(U4-TX2)") (class "Default")
      (node (ref "R17") (pin "1") (pinfunction "1_1") (pintype "passive"))
      (node (ref "U4") (pin "27") (pinfunction "TX2_27") (pintype "bidirectional"))
    )
    (net (code "56") (name "Net-(U4-TX_READY)") (class "Default")
      (node (ref "R26") (pin "1") (pinfunction "1_1") (pintype "passive"))
      (node (ref "U4") (pin "46") (pinfunction "TX_READY_46") (pintype "bidirectional"))
    )
    (net (code "57") (name "Net-(U4-TX{slash}MISO)") (class "Default")
      (node (ref "R21") (pin "1") (pinfunction "1_1") (pintype "passive"))
      (node (ref "U4") (pin "42") (pinfunction "TX/MISO_42") (pintype "bidirectional"))
    )
    (net (code "58") (name "Net-(U4-USB_D+)") (class "Default")
      (node (ref "R15") (pin "2") (pinfunction "2_2") (pintype "passive"))
      (node (ref "U4") (pin "40") (pinfunction "USB_D+_40") (pintype "bidirectional"))
    )
    (net (code "59") (name "Net-(U4-USB_D-)") (class "Default")
      (node (ref "R16") (pin "2") (pinfunction "2_2") (pintype "passive"))
      (node (ref "U4") (pin "39") (pinfunction "USB_D-_39") (pintype "bidirectional"))
    )
    (net (code "60") (name "Net-(U4-~{SAFEBOOT})") (class "Default")
      (node (ref "!SAFEBOOT_ZED!") (pin "1") (pinfunction "1_1") (pintype "bidirectional"))
      (node (ref "U4") (pin "50") (pinfunction "~{SAFEBOOT}_50") (pintype "bidirectional"))
    )
    (net (code "61") (name "RTK") (class "Default")
      (node (ref "J5") (pin "4") (pinfunction "4_4") (pintype "passive"))
      (node (ref "LED2") (pin "C") (pinfunction "C_C") (pintype "passive"))
      (node (ref "R23") (pin "2") (pinfunction "2_2") (pintype "passive"))
    )
    (net (code "62") (name "RXD1_NEO") (class "Default")
      (node (ref "J7") (pin "4") (pinfunction "4_4") (pintype "passive"))
      (node (ref "R6") (pin "2") (pinfunction "2_2") (pintype "passive"))
    )
    (net (code "63") (name "RXD1_ZED") (class "Default")
      (node (ref "J8") (pin "3") (pinfunction "3_3") (pintype "passive"))
      (node (ref "R22") (pin "2") (pinfunction "2_2") (pintype "passive"))
    )
    (net (code "64") (name "RXD2_NEO") (class "Default")
      (node (ref "J7") (pin "2") (pinfunction "2_2") (pintype "passive"))
      (node (ref "R5") (pin "2") (pinfunction "2_2") (pintype "passive"))
      (node (ref "TX2-RX2") (pin "2") (pinfunction "2_2") (pintype "passive"))
    )
    (net (code "65") (name "RXD2_ZED") (class "Default")
      (node (ref "J8") (pin "1") (pinfunction "1_1") (pintype "passive"))
      (node (ref "R18") (pin "2") (pinfunction "2_2") (pintype "passive"))
      (node (ref "RX2-TX2") (pin "1") (pinfunction "1_1") (pintype "passive"))
    )
    (net (code "66") (name "SCL") (class "Default")
      (node (ref "J10") (pin "4") (pinfunction "4_4") (pintype "passive"))
      (node (ref "J2") (pin "4") (pinfunction "4_4") (pintype "passive"))
      (node (ref "J4") (pin "4") (pinfunction "4_4") (pintype "passive"))
      (node (ref "J9") (pin "4") (pinfunction "4_4") (pintype "passive"))
      (node (ref "R20") (pin "2") (pinfunction "2_2") (pintype "passive"))
      (node (ref "R4") (pin "2") (pinfunction "2_2") (pintype "passive"))
      (node (ref "R7") (pin "1") (pinfunction "1_1") (pintype "passive"))
    )
    (net (code "67") (name "SDA") (class "Default")
      (node (ref "J10") (pin "3") (pinfunction "3_3") (pintype "passive"))
      (node (ref "J2") (pin "3") (pinfunction "3_3") (pintype "passive"))
      (node (ref "J4") (pin "3") (pinfunction "3_3") (pintype "passive"))
      (node (ref "J9") (pin "3") (pinfunction "3_3") (pintype "passive"))
      (node (ref "R19") (pin "2") (pinfunction "2_2") (pintype "passive"))
      (node (ref "R2") (pin "2") (pinfunction "2_2") (pintype "passive"))
      (node (ref "R8") (pin "1") (pinfunction "1_1") (pintype "passive"))
    )
    (net (code "68") (name "SHIELD_NEO") (class "Default")
      (node (ref "J6") (pin "SHLD1") (pinfunction "SHLD_SHLD1") (pintype "bidirectional"))
      (node (ref "J6") (pin "SHLD2") (pinfunction "SHLD_SHLD2") (pintype "bidirectional"))
      (node (ref "J6") (pin "SHLD3") (pinfunction "SHLD_SHLD3") (pintype "bidirectional"))
      (node (ref "J6") (pin "SHLD4") (pinfunction "SHLD_SHLD4") (pintype "bidirectional"))
      (node (ref "SHLD_NEO") (pin "2") (pinfunction "2_2") (pintype "passive"))
    )
    (net (code "69") (name "SHIELD_ZED") (class "Default")
      (node (ref "J3") (pin "SHLD1") (pinfunction "SHLD_SHLD1") (pintype "bidirectional"))
      (node (ref "J3") (pin "SHLD2") (pinfunction "SHLD_SHLD2") (pintype "bidirectional"))
      (node (ref "J3") (pin "SHLD3") (pinfunction "SHLD_SHLD3") (pintype "bidirectional"))
      (node (ref "J3") (pin "SHLD4") (pinfunction "SHLD_SHLD4") (pintype "bidirectional"))
      (node (ref "SHLD_ZED") (pin "2") (pinfunction "2_2") (pintype "passive"))
    )
    (net (code "70") (name "TP") (class "Default")
      (node (ref "J5") (pin "6") (pinfunction "6_6") (pintype "passive"))
      (node (ref "R25") (pin "2") (pinfunction "2_2") (pintype "passive"))
      (node (ref "R29") (pin "2") (pinfunction "2_2") (pintype "passive"))
    )
    (net (code "71") (name "TXD1_NEO") (class "Default")
      (node (ref "J7") (pin "3") (pinfunction "3_3") (pintype "passive"))
      (node (ref "R3") (pin "2") (pinfunction "2_2") (pintype "passive"))
    )
    (net (code "72") (name "TXD1_ZED") (class "Default")
      (node (ref "J8") (pin "4") (pinfunction "4_4") (pintype "passive"))
      (node (ref "R21") (pin "2") (pinfunction "2_2") (pintype "passive"))
    )
    (net (code "73") (name "TXD2_NEO") (class "Default")
      (node (ref "J7") (pin "1") (pinfunction "1_1") (pintype "passive"))
      (node (ref "R11") (pin "2") (pinfunction "2_2") (pintype "passive"))
      (node (ref "RX2-TX2") (pin "2") (pinfunction "2_2") (pintype "passive"))
    )
    (net (code "74") (name "TXD2_ZED") (class "Default")
      (node (ref "J8") (pin "2") (pinfunction "2_2") (pintype "passive"))
      (node (ref "R17") (pin "2") (pinfunction "2_2") (pintype "passive"))
      (node (ref "TX2-RX2") (pin "1") (pinfunction "1_1") (pintype "passive"))
    )
    (net (code "75") (name "TX_RDY") (class "Default")
      (node (ref "J5") (pin "7") (pinfunction "7_7") (pintype "passive"))
      (node (ref "R26") (pin "2") (pinfunction "2_2") (pintype "passive"))
    )
    (net (code "76") (name "VCC_RF") (class "Default")
      (node (ref "R14") (pin "2") (pinfunction "2_2") (pintype "passive"))
      (node (ref "U1") (pin "9") (pinfunction "VCC_RF_9") (pintype "output"))
    )
    (net (code "77") (name "V_BKCP") (class "Default")
      (node (ref "BT1") (pin "+") (pinfunction "+_+") (pintype "power_in"))
      (node (ref "R32") (pin "1") (pinfunction "1_1") (pintype "passive"))
      (node (ref "U4") (pin "36") (pinfunction "V_BKCP_36") (pintype "bidirectional"))
      (node (ref "V_BKCP") (pin "1") (pinfunction "1_1") (pintype "bidirectional"))
    )
    (net (code "78") (name "V_USB") (class "Default")
      (node (ref "D2") (pin "5") (pinfunction "5_5") (pintype "power_in"))
      (node (ref "D5") (pin "A") (pinfunction "A_A") (pintype "passive"))
      (node (ref "J3") (pin "VBUS1") (pinfunction "VBUS_VBUS1") (pintype "bidirectional"))
      (node (ref "J3") (pin "VBUS2") (pinfunction "VBUS_VBUS2") (pintype "bidirectional"))
    )
    (net (code "79") (name "V_USB_2") (class "Default")
      (node (ref "D4") (pin "5") (pinfunction "5_5") (pintype "power_in"))
      (node (ref "D6") (pin "A") (pinfunction "A_A") (pintype "passive"))
      (node (ref "J6") (pin "VBUS1") (pinfunction "VBUS_VBUS1") (pintype "bidirectional"))
      (node (ref "J6") (pin "VBUS2") (pinfunction "VBUS_VBUS2") (pintype "bidirectional"))
    )
    (net (code "80") (name "unconnected-(U1-ANT_DETECT-Pad15)") (class "Default")
      (node (ref "U1") (pin "15") (pinfunction "ANT_DETECT_15") (pintype "input"))
    )
    (net (code "81") (name "unconnected-(U1-ANT_OFF-Pad14)") (class "Default")
      (node (ref "U1") (pin "14") (pinfunction "ANT_OFF_14") (pintype "output"))
    )
    (net (code "82") (name "unconnected-(U1-D_SEL-Pad2)") (class "Default")
      (node (ref "U1") (pin "2") (pinfunction "D_SEL_2") (pintype "input"))
    )
    (net (code "83") (name "unconnected-(U1-~{ANT_SHORT}-Pad16)") (class "Default")
      (node (ref "U1") (pin "16") (pinfunction "~{ANT_SHORT}_16") (pintype "output"))
    )
    (net (code "84") (name "unconnected-(U2-NC-Pad4)") (class "Default")
      (node (ref "U2") (pin "4") (pinfunction "NC_4") (pintype "no_connect"))
    )
    (net (code "85") (name "unconnected-(U4-ANT_DETECT-Pad4)") (class "Default")
      (node (ref "U4") (pin "4") (pinfunction "ANT_DETECT_4") (pintype "bidirectional"))
    )
    (net (code "86") (name "unconnected-(U4-ANT_OFF-Pad5)") (class "Default")
      (node (ref "U4") (pin "5") (pinfunction "ANT_OFF_5") (pintype "bidirectional"))
    )
    (net (code "87") (name "unconnected-(U4-D_SEL-Pad47)") (class "Default")
      (node (ref "U4") (pin "47") (pinfunction "D_SEL_47") (pintype "bidirectional"))
    )
    (net (code "88") (name "unconnected-(U4-V_RF-Pad7)") (class "Default")
      (node (ref "U4") (pin "7") (pinfunction "V_RF_7") (pintype "bidirectional"))
    )
    (net (code "89") (name "unconnected-(U4-~{ANT_SHORT}-Pad6)") (class "Default")
      (node (ref "U4") (pin "6") (pinfunction "~{ANT_SHORT}_6") (pintype "bidirectional"))
    )
  )
)
